# XInC2_Dev_-_SCH.net
KiCad netlist of a schematic drawn in Altium Designer
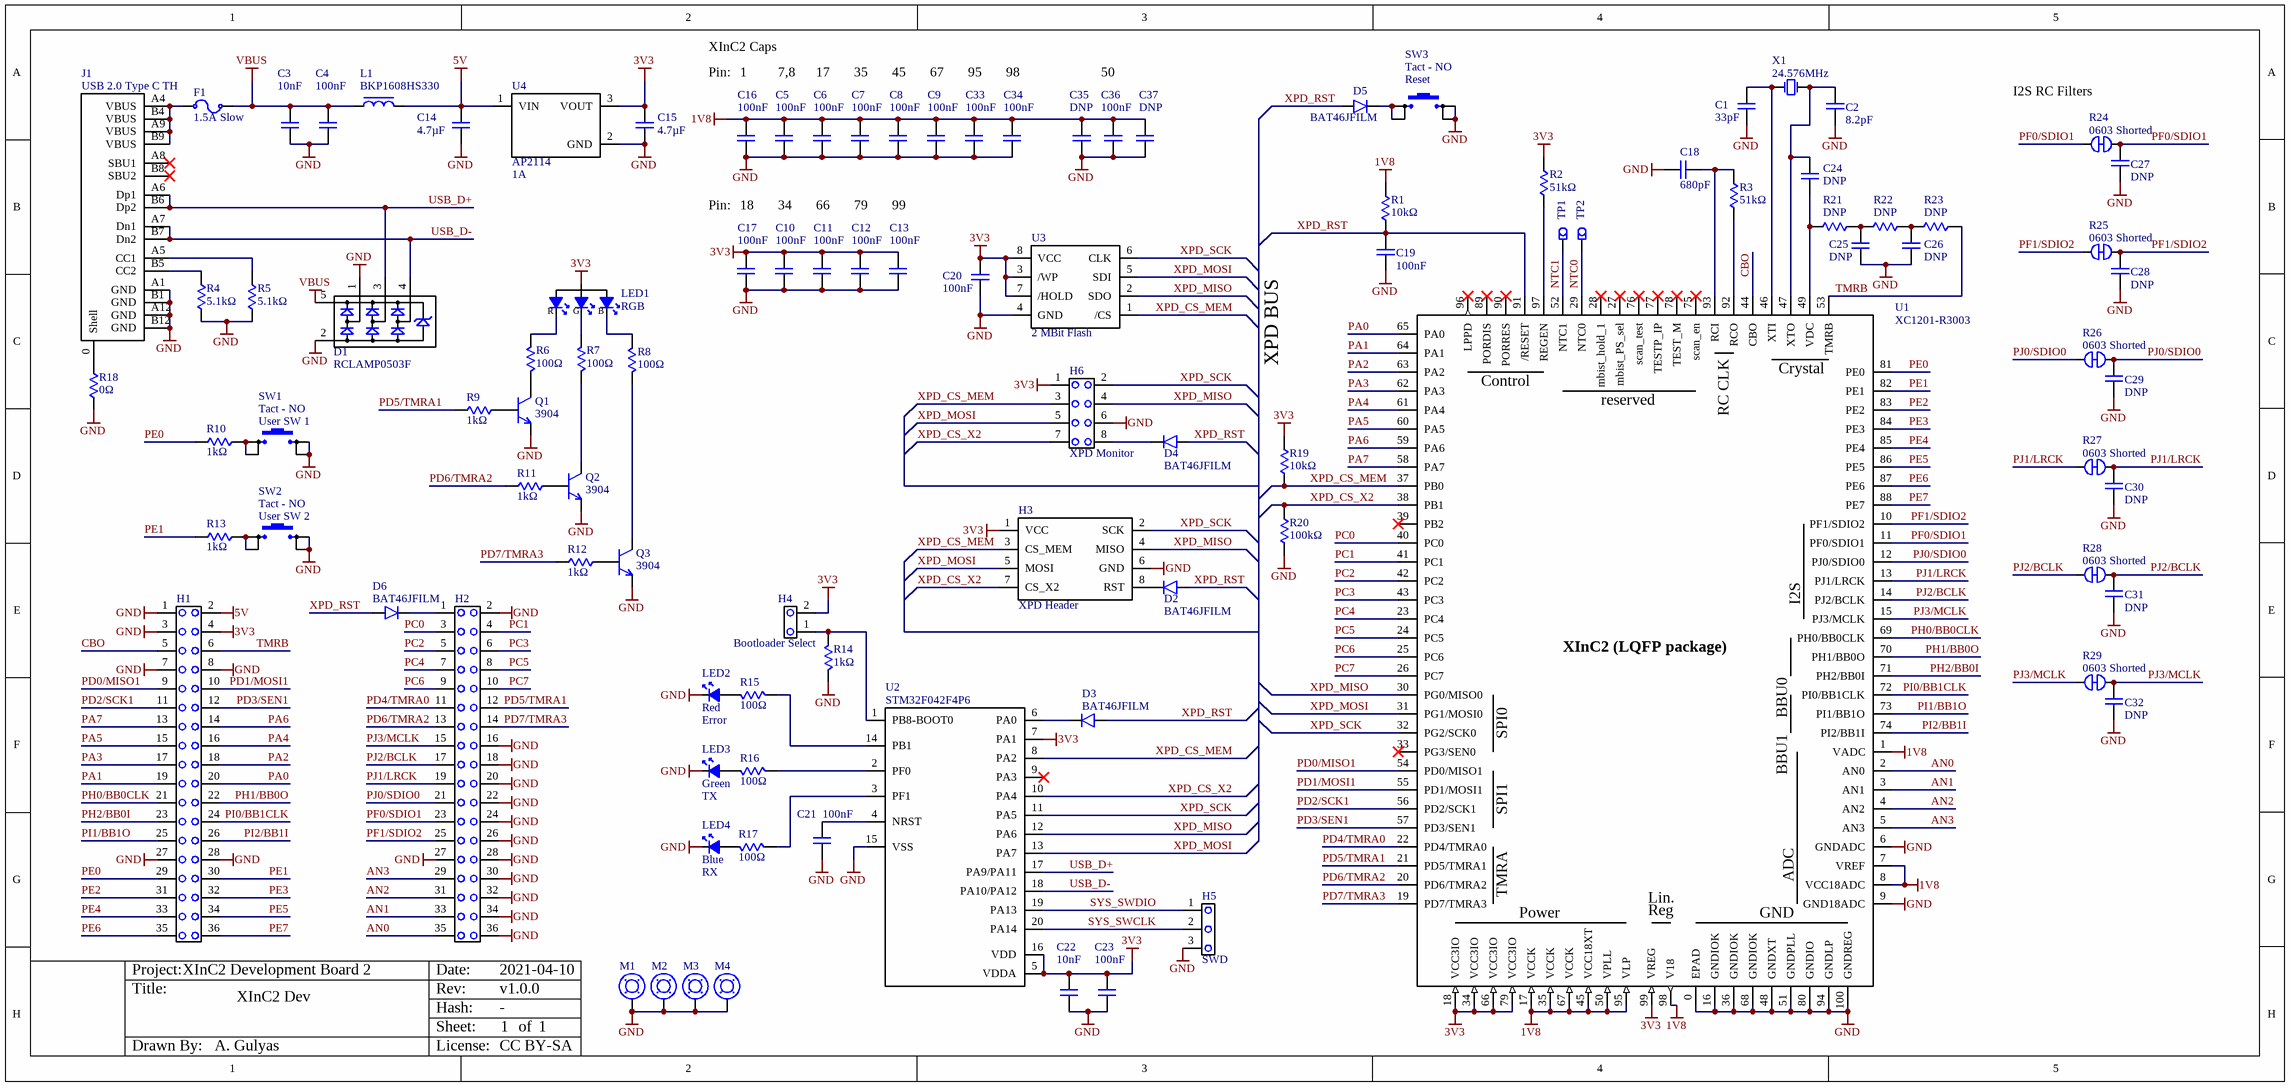
[diagram p0: XInC2 Dev - SCH.SchDoc]

(export (version "E")
  (design (tool "Eeschema 10.0.6"))
  (components
    (comp (ref "C1")
      (value "33pF")
      (footprint "0603 - C")
      (description "CAP CER 33PF 50V C0G/NPO 0603")
      (fields (field (name "MFG") "Yageo") (field (name "TOLERANCE") "±5%"))
      (libsource (lib "Public Library") (part "C - 0603 - 33pF - 16V_1"))
    )
    (comp (ref "C2")
      (value "8.2pF")
      (footprint "0603 - C")
      (description "CAP CER 8.2PF 50V NPO 0603")
      (fields (field (name "MFG") "Yageo") (field (name "TOLERANCE") "±0.25pF"))
      (libsource (lib "Public Library") (part "C - 0603 - 8.2pF - 50V"))
    )
    (comp (ref "C3")
      (value "10nF")
      (footprint "0603 - C")
      (description "CAP CER 10000PF 50V X7R 0603")
      (fields (field (name "MFG") "Yageo") (field (name "TOLERANCE") "±5%"))
      (libsource (lib "Public Library") (part "C - 0603 - 10nF - 50V"))
    )
    (comp (ref "C4")
      (value "100nF")
      (footprint "0603 - C")
      (description "CAP CER 0.1UF 16V X7R 0603")
      (fields (field (name "MFG") "Yageo") (field (name "TOLERANCE") "±10%"))
      (libsource (lib "Public Library") (part "C - 0603 - 100nF - 16V"))
    )
    (comp (ref "C5")
      (value "100nF")
      (footprint "0603 - C")
      (description "CAP CER 0.1UF 16V X7R 0603")
      (fields (field (name "MFG") "Yageo") (field (name "TOLERANCE") "±10%"))
      (libsource (lib "Public Library") (part "C - 0603 - 100nF - 16V"))
    )
    (comp (ref "C6")
      (value "100nF")
      (footprint "0603 - C")
      (description "CAP CER 0.1UF 16V X7R 0603")
      (fields (field (name "MFG") "Yageo") (field (name "TOLERANCE") "±10%"))
      (libsource (lib "Public Library") (part "C - 0603 - 100nF - 16V"))
    )
    (comp (ref "C7")
      (value "100nF")
      (footprint "0603 - C")
      (description "CAP CER 0.1UF 16V X7R 0603")
      (fields (field (name "MFG") "Yageo") (field (name "TOLERANCE") "±10%"))
      (libsource (lib "Public Library") (part "C - 0603 - 100nF - 16V"))
    )
    (comp (ref "C8")
      (value "100nF")
      (footprint "0603 - C")
      (description "CAP CER 0.1UF 16V X7R 0603")
      (fields (field (name "MFG") "Yageo") (field (name "TOLERANCE") "±10%"))
      (libsource (lib "Public Library") (part "C - 0603 - 100nF - 16V"))
    )
    (comp (ref "C9")
      (value "100nF")
      (footprint "0603 - C")
      (description "CAP CER 0.1UF 16V X7R 0603")
      (fields (field (name "MFG") "Yageo") (field (name "TOLERANCE") "±10%"))
      (libsource (lib "Public Library") (part "C - 0603 - 100nF - 16V"))
    )
    (comp (ref "C10")
      (value "100nF")
      (footprint "0603 - C")
      (description "CAP CER 0.1UF 16V X7R 0603")
      (fields (field (name "MFG") "Yageo") (field (name "TOLERANCE") "±10%"))
      (libsource (lib "Public Library") (part "C - 0603 - 100nF - 16V"))
    )
    (comp (ref "C11")
      (value "100nF")
      (footprint "0603 - C")
      (description "CAP CER 0.1UF 16V X7R 0603")
      (fields (field (name "MFG") "Yageo") (field (name "TOLERANCE") "±10%"))
      (libsource (lib "Public Library") (part "C - 0603 - 100nF - 16V"))
    )
    (comp (ref "C12")
      (value "100nF")
      (footprint "0603 - C")
      (description "CAP CER 0.1UF 16V X7R 0603")
      (fields (field (name "MFG") "Yageo") (field (name "TOLERANCE") "±10%"))
      (libsource (lib "Public Library") (part "C - 0603 - 100nF - 16V"))
    )
    (comp (ref "C13")
      (value "100nF")
      (footprint "0603 - C")
      (description "CAP CER 0.1UF 16V X7R 0603")
      (fields (field (name "MFG") "Yageo") (field (name "TOLERANCE") "±10%"))
      (libsource (lib "Public Library") (part "C - 0603 - 100nF - 16V"))
    )
    (comp (ref "C14")
      (value "4.7µF")
      (footprint "0603 - C")
      (description "CAP CER 4.7UF 10V X5R 0603")
      (fields (field (name "MFG") "Yageo") (field (name "TOLERANCE") "±20%"))
      (libsource (lib "Public Library") (part "C - 0603 - 4.7uF - 10V"))
    )
    (comp (ref "C15")
      (value "4.7µF")
      (footprint "0603 - C")
      (description "CAP CER 4.7UF 10V X5R 0603")
      (fields (field (name "MFG") "Yageo") (field (name "TOLERANCE") "±20%"))
      (libsource (lib "Public Library") (part "C - 0603 - 4.7uF - 10V"))
    )
    (comp (ref "C16")
      (value "100nF")
      (footprint "0603 - C")
      (description "CAP CER 0.1UF 16V X7R 0603")
      (fields (field (name "MFG") "Yageo") (field (name "TOLERANCE") "±10%"))
      (libsource (lib "Public Library") (part "C - 0603 - 100nF - 16V"))
    )
    (comp (ref "C17")
      (value "100nF")
      (footprint "0603 - C")
      (description "CAP CER 0.1UF 16V X7R 0603")
      (fields (field (name "MFG") "Yageo") (field (name "TOLERANCE") "±10%"))
      (libsource (lib "Public Library") (part "C - 0603 - 100nF - 16V"))
    )
    (comp (ref "C18")
      (value "680pF")
      (footprint "0603 - C")
      (description "CAP CER 680PF 50V X7R 0603")
      (fields (field (name "MFG") "Yageo") (field (name "TOLERANCE") "±10%"))
      (libsource (lib "Public Library") (part "C - 0603 - 680pF - 50V"))
    )
    (comp (ref "C19")
      (value "100nF")
      (footprint "0603 - C")
      (description "CAP CER 0.1UF 16V X7R 0603")
      (fields (field (name "MFG") "Yageo") (field (name "TOLERANCE") "±10%"))
      (libsource (lib "Public Library") (part "C - 0603 - 100nF - 16V"))
    )
    (comp (ref "C20")
      (value "100nF")
      (footprint "0603 - C")
      (description "CAP CER 0.1UF 16V X7R 0603")
      (fields (field (name "MFG") "Yageo") (field (name "TOLERANCE") "±10%"))
      (libsource (lib "Public Library") (part "C - 0603 - 100nF - 16V"))
    )
    (comp (ref "C21")
      (value "100nF")
      (footprint "0603 - C")
      (description "CAP CER 0.1UF 16V X7R 0603")
      (fields (field (name "MFG") "Yageo") (field (name "TOLERANCE") "±10%"))
      (libsource (lib "Public Library") (part "C - 0603 - 100nF - 16V"))
    )
    (comp (ref "C22")
      (value "10nF")
      (footprint "0603 - C")
      (description "CAP CER 10000PF 50V X7R 0603")
      (fields (field (name "MFG") "Yageo") (field (name "TOLERANCE") "±5%"))
      (libsource (lib "Public Library") (part "C - 0603 - 10nF - 50V"))
    )
    (comp (ref "C23")
      (value "100nF")
      (footprint "0603 - C")
      (description "CAP CER 0.1UF 16V X7R 0603")
      (fields (field (name "MFG") "Yageo") (field (name "TOLERANCE") "±10%"))
      (libsource (lib "Public Library") (part "C - 0603 - 100nF - 16V"))
    )
    (comp (ref "C24")
      (value "DNP")
      (footprint "0603 - C - DNP")
      (description "DNP C 0603")
      (libsource (lib "Public Library") (part "C - 0603 - DNP"))
    )
    (comp (ref "C25")
      (value "DNP")
      (footprint "0603 - C - DNP")
      (description "DNP C 0603")
      (libsource (lib "Public Library") (part "C - 0603 - DNP"))
    )
    (comp (ref "C26")
      (value "DNP")
      (footprint "0603 - C - DNP")
      (description "DNP C 0603")
      (libsource (lib "Public Library") (part "C - 0603 - DNP"))
    )
    (comp (ref "C27")
      (value "DNP")
      (footprint "0603 - C - DNP")
      (description "DNP C 0603")
      (libsource (lib "Public Library") (part "C - 0603 - DNP"))
    )
    (comp (ref "C28")
      (value "DNP")
      (footprint "0603 - C - DNP")
      (description "DNP C 0603")
      (libsource (lib "Public Library") (part "C - 0603 - DNP"))
    )
    (comp (ref "C29")
      (value "DNP")
      (footprint "0603 - C - DNP")
      (description "DNP C 0603")
      (libsource (lib "Public Library") (part "C - 0603 - DNP"))
    )
    (comp (ref "C30")
      (value "DNP")
      (footprint "0603 - C - DNP")
      (description "DNP C 0603")
      (libsource (lib "Public Library") (part "C - 0603 - DNP"))
    )
    (comp (ref "C31")
      (value "DNP")
      (footprint "0603 - C - DNP")
      (description "DNP C 0603")
      (libsource (lib "Public Library") (part "C - 0603 - DNP"))
    )
    (comp (ref "C32")
      (value "DNP")
      (footprint "0603 - C - DNP")
      (description "DNP C 0603")
      (libsource (lib "Public Library") (part "C - 0603 - DNP"))
    )
    (comp (ref "C33")
      (value "100nF")
      (footprint "0603 - C")
      (description "CAP CER 0.1UF 16V X7R 0603")
      (fields (field (name "MFG") "Yageo") (field (name "TOLERANCE") "±10%"))
      (libsource (lib "Public Library") (part "C - 0603 - 100nF - 16V"))
    )
    (comp (ref "C34")
      (value "100nF")
      (footprint "0603 - C")
      (description "CAP CER 0.1UF 16V X7R 0603")
      (fields (field (name "MFG") "Yageo") (field (name "TOLERANCE") "±10%"))
      (libsource (lib "Public Library") (part "C - 0603 - 100nF - 16V"))
    )
    (comp (ref "C35")
      (value "DNP")
      (footprint "0603 - C - DNP")
      (description "DNP C 0603")
      (libsource (lib "Public Library") (part "C - 0603 - DNP"))
    )
    (comp (ref "C36")
      (value "100nF")
      (footprint "0603 - C")
      (description "CAP CER 0.1UF 16V X7R 0603")
      (fields (field (name "MFG") "Yageo") (field (name "TOLERANCE") "±10%"))
      (libsource (lib "Public Library") (part "C - 0603 - 100nF - 16V"))
    )
    (comp (ref "C37")
      (value "DNP")
      (footprint "0603 - C - DNP")
      (description "DNP C 0603")
      (libsource (lib "Public Library") (part "C - 0603 - DNP"))
    )
    (comp (ref "D1")
      (value "RCLAMP0503F")
      (footprint "SOT 353")
      (description "TVS DIODE 5V 25V SC70-5")
      (fields (field (name "MFG") "Semtech Corp"))
      (libsource (lib "Public Library") (part "TVS - USB - RCLAMP0503F"))
    )
    (comp (ref "D2")
      (value "BAT46JFILM")
      (footprint "SOD 323")
      (description "DIODE SCHOTTKY 100V 150MA SOD323")
      (fields (field (name "MFG") "ST"))
      (libsource (lib "Public Library") (part "D - BAT46JFILM"))
    )
    (comp (ref "D3")
      (value "BAT46JFILM")
      (footprint "SOD 323")
      (description "DIODE SCHOTTKY 100V 150MA SOD323")
      (fields (field (name "MFG") "ST"))
      (libsource (lib "Public Library") (part "D - BAT46JFILM"))
    )
    (comp (ref "D4")
      (value "BAT46JFILM")
      (footprint "SOD 323 and 0603")
      (description "DIODE SCHOTTKY 100V 150MA SOD323")
      (fields (field (name "MFG") "ST"))
      (libsource (lib "Public Library") (part "D - BAT46JFILM"))
    )
    (comp (ref "D5")
      (value "BAT46JFILM")
      (footprint "SOD 323")
      (description "DIODE SCHOTTKY 100V 150MA SOD323")
      (fields (field (name "MFG") "ST"))
      (libsource (lib "Public Library") (part "D - BAT46JFILM"))
    )
    (comp (ref "D6")
      (value "BAT46JFILM")
      (footprint "SOD 323")
      (description "DIODE SCHOTTKY 100V 150MA SOD323")
      (fields (field (name "MFG") "ST"))
      (libsource (lib "Public Library") (part "D - BAT46JFILM"))
    )
    (comp (ref "F1")
      (value "1.5A Slow")
      (footprint "Fuse - C1T Series")
      (description "FUSE 1.5A 63VAC/DC SLOW 1206")
      (fields (field (name "MFG") "Bel Fuse Inc."))
      (libsource (lib "Public Library") (part "Fuse - 1.5A slow"))
    )
    (comp (ref "H1")
      (value "SSQ-118-03-T-D")
      (footprint "H - 100mil - 2x18 - Stack - bottom insert")
      (description "CONN RCPT 36POS 0.1 TIN PCB")
      (fields (field (name "MFG") "Samtec"))
      (libsource (lib "Public Library") (part "H - 100mil - Stack - 2x18"))
    )
    (comp (ref "H2")
      (value "SSQ-118-03-T-D")
      (footprint "H - 100mil - 2x18 - Stack - bottom insert")
      (description "CONN RCPT 36POS 0.1 TIN PCB")
      (fields (field (name "MFG") "Samtec"))
      (libsource (lib "Public Library") (part "H - 100mil - Stack - 2x18"))
    )
    (comp (ref "H3")
      (value "XPD Header")
      (footprint "H - XPD")
      (description "CONN HEADER SMD 8POS 1.27MM")
      (fields (field (name "MFG") "Samtec Inc."))
      (libsource (lib "Public Library") (part "H - XPD - SMT"))
    )
    (comp (ref "H4")
      (value "H - 100mil - M - TH - 1x2")
      (footprint "H - 100mil - 1x2 - TH")
      (description "CONN HEADER VERT 2POS 2.54MM")
      (fields (field (name "PURPOSE") "Bootloader Select"))
      (libsource (lib "Public Library") (part "H - 100mil - M - TH - 1x2"))
    )
    (comp (ref "H5")
      (value "H - 100mil - M - TH - 1x3")
      (footprint "H - 100mil - 1x3 - TH")
      (description "CONN HEADER VERT 3POS 2.54MM")
      (fields (field (name "PURPOSE") "SWD"))
      (libsource (lib "Public Library") (part "H - 100mil - M - TH - 1x3"))
    )
    (comp (ref "H6")
      (value "H - 100mil - M - TH - 2x4")
      (footprint "H - 100mil - 2x4 - TH - DNP")
      (fields (field (name "PURPOSE") "XPD Monitor"))
      (libsource (lib "Public Library") (part "H - 100mil - M - TH - 2x4"))
    )
    (comp (ref "J1")
      (value "USB 2.0 Type C TH")
      (footprint "Jack - USB C - 2.0 - TH")
      (description "CONN RCPT USB2.0 TYPEC 16POS")
      (fields (field (name "MFG") "GCT"))
      (libsource (lib "Public Library") (part "Jack - USB C - USB4085"))
    )
    (comp (ref "L1")
      (value "BKP1608HS330")
      (footprint "0603 - R")
      (description "FERRITE BEAD 33 OHM 0603 1LN")
      (fields (field (name "MFG") "Taiyo Yuden"))
      (libsource (lib "Public Library") (part "Ferrite - 0603 - 33 ohm"))
    )
    (comp (ref "LED1")
      (value "RGB")
      (footprint "LED - RGB - 0606")
      (description "LED RGB CLEAR 4SMD")
      (fields (field (name "MFG") "Everlight Electronics"))
      (libsource (lib "Public Library") (part "LED - RGB"))
    )
    (comp (ref "LED2")
      (value "Red")
      (footprint "LED - Red - 0603")
      (description "LED RED CLEAR CHIP SMD")
      (fields (field (name "MFG") "Lite-On Inc.") (field (name "PURPOSE") "Error"))
      (libsource (lib "Public Library") (part "LED - Red"))
    )
    (comp (ref "LED3")
      (value "Green")
      (footprint "LED - Green - 0603")
      (description "LED GREEN CLEAR CHIP SMD")
      (fields (field (name "MFG") "Lite-On Inc.") (field (name "PURPOSE") "TX"))
      (libsource (lib "Public Library") (part "LED - Green"))
    )
    (comp (ref "LED4")
      (value "Blue")
      (footprint "LED - Blue - 0603")
      (description "LED BLUE CLEAR CHIP SMD")
      (fields (field (name "MFG") "Lite-On Inc.") (field (name "PURPOSE") "RX"))
      (libsource (lib "Public Library") (part "LED - Blue"))
    )
    (comp (ref "M1")
      (value "Mech - Bolt Hole - M3")
      (footprint "Bolt Hole - M3")
      (libsource (lib "Public Library") (part "Mech - Bolt Hole - M3"))
    )
    (comp (ref "M2")
      (value "Mech - Bolt Hole - M3")
      (footprint "Bolt Hole - M3")
      (libsource (lib "Public Library") (part "Mech - Bolt Hole - M3"))
    )
    (comp (ref "M3")
      (value "Mech - Bolt Hole - M3")
      (footprint "Bolt Hole - M3")
      (libsource (lib "Public Library") (part "Mech - Bolt Hole - M3"))
    )
    (comp (ref "M4")
      (value "Mech - Bolt Hole - M3")
      (footprint "Bolt Hole - M3")
      (libsource (lib "Public Library") (part "Mech - Bolt Hole - M3"))
    )
    (comp (ref "Q1")
      (value "3904")
      (footprint "SOT 23 - NPN - MCC")
      (description "TRANS NPN 40V 0.2A SOT23")
      (fields (field (name "MFG") "Micro Commercial"))
      (libsource (lib "Public Library") (part "Q - NPN - MMBT3904"))
    )
    (comp (ref "Q2")
      (value "3904")
      (footprint "SOT 23 - NPN - MCC")
      (description "TRANS NPN 40V 0.2A SOT23")
      (fields (field (name "MFG") "Micro Commercial"))
      (libsource (lib "Public Library") (part "Q - NPN - MMBT3904"))
    )
    (comp (ref "Q3")
      (value "3904")
      (footprint "SOT 23 - NPN - MCC")
      (description "TRANS NPN 40V 0.2A SOT23")
      (fields (field (name "MFG") "Micro Commercial"))
      (libsource (lib "Public Library") (part "Q - NPN - MMBT3904"))
    )
    (comp (ref "R1")
      (value "10kΩ")
      (footprint "0603 - R")
      (description "RES SMD 10K OHM 5% 1/10W 0603")
      (fields (field (name "MFG") "Yageo") (field (name "POWER") "0.1W"))
      (libsource (lib "Public Library") (part "R - 0603 - 10k"))
    )
    (comp (ref "R2")
      (value "51kΩ")
      (footprint "0603 - R")
      (description "RES SMD 51K OHM 5% 1/10W 0603")
      (fields (field (name "MFG") "Yageo") (field (name "POWER") "0.1W"))
      (libsource (lib "Public Library") (part "R - 0603 - 51k"))
    )
    (comp (ref "R3")
      (value "51kΩ")
      (footprint "0603 - R")
      (description "RES SMD 51K OHM 5% 1/10W 0603")
      (fields (field (name "MFG") "Yageo") (field (name "POWER") "0.1W"))
      (libsource (lib "Public Library") (part "R - 0603 - 51k"))
    )
    (comp (ref "R4")
      (value "5.1kΩ")
      (footprint "0603 - R")
      (description "RES SMD 5.1K OHM 5% 1/10W 0603")
      (fields (field (name "MFG") "Yageo") (field (name "POWER") "0.1W"))
      (libsource (lib "Public Library") (part "R - 0603 - 5.1k"))
    )
    (comp (ref "R5")
      (value "5.1kΩ")
      (footprint "0603 - R")
      (description "RES SMD 5.1K OHM 5% 1/10W 0603")
      (fields (field (name "MFG") "Yageo") (field (name "POWER") "0.1W"))
      (libsource (lib "Public Library") (part "R - 0603 - 5.1k"))
    )
    (comp (ref "R6")
      (value "100Ω")
      (footprint "0603 - R")
      (description "RES SMD 100 OHM 5% 1/10W 0603")
      (fields (field (name "MFG") "Yageo") (field (name "POWER") "0.1W"))
      (libsource (lib "Public Library") (part "R - 0603 - 100R"))
    )
    (comp (ref "R7")
      (value "100Ω")
      (footprint "0603 - R")
      (description "RES SMD 100 OHM 5% 1/10W 0603")
      (fields (field (name "MFG") "Yageo") (field (name "POWER") "0.1W"))
      (libsource (lib "Public Library") (part "R - 0603 - 100R"))
    )
    (comp (ref "R8")
      (value "100Ω")
      (footprint "0603 - R")
      (description "RES SMD 100 OHM 5% 1/10W 0603")
      (fields (field (name "MFG") "Yageo") (field (name "POWER") "0.1W"))
      (libsource (lib "Public Library") (part "R - 0603 - 100R"))
    )
    (comp (ref "R9")
      (value "1kΩ")
      (footprint "0603 - R")
      (description "RES SMD 1K OHM 5% 1/10W 0603")
      (fields (field (name "MFG") "Yageo") (field (name "POWER") "0.1W"))
      (libsource (lib "Public Library") (part "R - 0603 - 1k"))
    )
    (comp (ref "R10")
      (value "1kΩ")
      (footprint "0603 - R")
      (description "RES SMD 1K OHM 5% 1/10W 0603")
      (fields (field (name "MFG") "Yageo") (field (name "POWER") "0.1W"))
      (libsource (lib "Public Library") (part "R - 0603 - 1k"))
    )
    (comp (ref "R11")
      (value "1kΩ")
      (footprint "0603 - R")
      (description "RES SMD 1K OHM 5% 1/10W 0603")
      (fields (field (name "MFG") "Yageo") (field (name "POWER") "0.1W"))
      (libsource (lib "Public Library") (part "R - 0603 - 1k"))
    )
    (comp (ref "R12")
      (value "1kΩ")
      (footprint "0603 - R")
      (description "RES SMD 1K OHM 5% 1/10W 0603")
      (fields (field (name "MFG") "Yageo") (field (name "POWER") "0.1W"))
      (libsource (lib "Public Library") (part "R - 0603 - 1k"))
    )
    (comp (ref "R13")
      (value "1kΩ")
      (footprint "0603 - R")
      (description "RES SMD 1K OHM 5% 1/10W 0603")
      (fields (field (name "MFG") "Yageo") (field (name "POWER") "0.1W"))
      (libsource (lib "Public Library") (part "R - 0603 - 1k"))
    )
    (comp (ref "R14")
      (value "1kΩ")
      (footprint "0603 - R")
      (description "RES SMD 1K OHM 5% 1/10W 0603")
      (fields (field (name "MFG") "Yageo") (field (name "POWER") "0.1W"))
      (libsource (lib "Public Library") (part "R - 0603 - 1k"))
    )
    (comp (ref "R15")
      (value "100Ω")
      (footprint "0603 - R")
      (description "RES SMD 100 OHM 5% 1/10W 0603")
      (fields (field (name "MFG") "Yageo") (field (name "POWER") "0.1W"))
      (libsource (lib "Public Library") (part "R - 0603 - 100R"))
    )
    (comp (ref "R16")
      (value "100Ω")
      (footprint "0603 - R")
      (description "RES SMD 100 OHM 5% 1/10W 0603")
      (fields (field (name "MFG") "Yageo") (field (name "POWER") "0.1W"))
      (libsource (lib "Public Library") (part "R - 0603 - 100R"))
    )
    (comp (ref "R17")
      (value "100Ω")
      (footprint "0603 - R")
      (description "RES SMD 100 OHM 5% 1/10W 0603")
      (fields (field (name "MFG") "Yageo") (field (name "POWER") "0.1W"))
      (libsource (lib "Public Library") (part "R - 0603 - 100R"))
    )
    (comp (ref "R18")
      (value "0Ω")
      (footprint "0603 - R")
      (description "RES SMD 0 OHM JUMPER 1/10W 0603")
      (fields (field (name "MFG") "Yageo") (field (name "POWER") "0.1W"))
      (libsource (lib "Public Library") (part "Jumper - 0603"))
    )
    (comp (ref "R19")
      (value "10kΩ")
      (footprint "0603 - R")
      (description "RES SMD 10K OHM 5% 1/10W 0603")
      (fields (field (name "MFG") "Yageo") (field (name "POWER") "0.1W"))
      (libsource (lib "Public Library") (part "R - 0603 - 10k"))
    )
    (comp (ref "R20")
      (value "100kΩ")
      (footprint "0603 - R")
      (description "RES SMD 100K OHM 5% 1/10W 0603")
      (fields (field (name "MFG") "Yageo") (field (name "POWER") "0.1W"))
      (libsource (lib "Public Library") (part "R - 0603 - 100k"))
    )
    (comp (ref "R21")
      (value "DNP")
      (footprint "0603 - R - DNP")
      (description "DNP R 0603")
      (libsource (lib "Public Library") (part "R - 0603 - DNP"))
    )
    (comp (ref "R22")
      (value "DNP")
      (footprint "0603 - R - DNP")
      (description "DNP R 0603")
      (libsource (lib "Public Library") (part "R - 0603 - DNP"))
    )
    (comp (ref "R23")
      (value "DNP")
      (footprint "0603 - R - DNP")
      (description "DNP R 0603")
      (libsource (lib "Public Library") (part "R - 0603 - DNP"))
    )
    (comp (ref "R24")
      (value "0603 Shorted")
      (footprint "0603 - R - shorted jumper")
      (description "DNP: 0603 Resistor with the pads shorted")
      (fields (field (name "MFG") "Yageo") (field (name "POWER") "0.1W"))
      (libsource (lib "Public Library") (part "Jumper - 0603 - Shorted"))
    )
    (comp (ref "R25")
      (value "0603 Shorted")
      (footprint "0603 - R - shorted jumper")
      (description "DNP: 0603 Resistor with the pads shorted")
      (fields (field (name "MFG") "Yageo") (field (name "POWER") "0.1W"))
      (libsource (lib "Public Library") (part "Jumper - 0603 - Shorted"))
    )
    (comp (ref "R26")
      (value "0603 Shorted")
      (footprint "0603 - R - shorted jumper")
      (description "DNP: 0603 Resistor with the pads shorted")
      (fields (field (name "MFG") "Yageo") (field (name "POWER") "0.1W"))
      (libsource (lib "Public Library") (part "Jumper - 0603 - Shorted"))
    )
    (comp (ref "R27")
      (value "0603 Shorted")
      (footprint "0603 - R - shorted jumper")
      (description "DNP: 0603 Resistor with the pads shorted")
      (fields (field (name "MFG") "Yageo") (field (name "POWER") "0.1W"))
      (libsource (lib "Public Library") (part "Jumper - 0603 - Shorted"))
    )
    (comp (ref "R28")
      (value "0603 Shorted")
      (footprint "0603 - R - shorted jumper")
      (description "DNP: 0603 Resistor with the pads shorted")
      (fields (field (name "MFG") "Yageo") (field (name "POWER") "0.1W"))
      (libsource (lib "Public Library") (part "Jumper - 0603 - Shorted"))
    )
    (comp (ref "R29")
      (value "0603 Shorted")
      (footprint "0603 - R - shorted jumper")
      (description "DNP: 0603 Resistor with the pads shorted")
      (fields (field (name "MFG") "Yageo") (field (name "POWER") "0.1W"))
      (libsource (lib "Public Library") (part "Jumper - 0603 - Shorted"))
    )
    (comp (ref "SW1")
      (value "Tact - NO")
      (footprint "SW - Tact - SMT")
      (description "SWITCH TACTILE SPST-NO 3VA 28V")
      (fields (field (name "PURPOSE") "User SW 1") (field (name "MFG") "NKK Switches"))
      (libsource (lib "Public Library") (part "SW - Tactile - HP0315AFKP2-R"))
    )
    (comp (ref "SW2")
      (value "Tact - NO")
      (footprint "SW - Tact - SMT")
      (description "SWITCH TACTILE SPST-NO 3VA 28V")
      (fields (field (name "PURPOSE") "User SW 2") (field (name "MFG") "NKK Switches"))
      (libsource (lib "Public Library") (part "SW - Tactile - HP0315AFKP2-R"))
    )
    (comp (ref "SW3")
      (value "Tact - NO")
      (footprint "SW - Tact - SMT")
      (description "SWITCH TACTILE SPST-NO 3VA 28V")
      (fields (field (name "PURPOSE") "Reset") (field (name "MFG") "NKK Switches"))
      (libsource (lib "Public Library") (part "SW - Tactile - HP0315AFKP2-R"))
    )
    (comp (ref "TP1")
      (value "Signal")
      (footprint "TP - TH - 0.6mm")
      (libsource (lib "Public Library") (part "TP - TH - 0.6 mm"))
    )
    (comp (ref "TP2")
      (value "Signal")
      (footprint "TP - TH - 0.6mm")
      (libsource (lib "Public Library") (part "TP - TH - 0.6 mm"))
    )
    (comp (ref "U1")
      (value "XC1201-R3003")
      (footprint "XInC2 LQFP 100")
      (description "XInC2 Multi-Threaded µC LQFP")
      (fields (field (name "MFG") "Eleven Engineering"))
      (libsource (lib "Public Library") (part "uC - XInC2 - LQFP"))
    )
    (comp (ref "U2")
      (value "STM32F042F4P6")
      (footprint "TSSOP 20")
      (description "IC MCU 32BIT 16KB FLASH 20TSSOP")
      (fields (field (name "MFG") "ST"))
      (libsource (lib "Public Library") (part "uC - STM32F042F4P6"))
    )
    (comp (ref "U3")
      (value "2 MBit Flash")
      (footprint "SOIC 8")
      (description "IC FLASH 2MBIT SPI 104MHZ 8SOIC")
      (fields (field (name "MFG") "Winbond Electronics"))
      (libsource (lib "Public Library") (part "Mem - Flash - 2 MBit - W25Q20CL"))
    )
    (comp (ref "U4")
      (value "AP2114")
      (footprint "SOT 223")
      (description "IC REG LINEAR 3.3V 1A SOT223")
      (fields (field (name "MFG") "Diodes Inc") (field (name "CURRENT - OUTPUT") "1A"))
      (libsource (lib "Public Library") (part "Reg - Lin - 3.3V - AP2114"))
    )
    (comp (ref "X1")
      (value "24.576MHz")
      (footprint "X - HC-49/US")
      (description "CRYSTAL 24.576MHZ SMD")
      (fields (field (name "MFG") "Huijing"))
      (libsource (lib "Public Library") (part "X - 20 MHz - HJ24.576"))
    )
  )
  (nets
    (net (code "1") (name "/AN0") (class "Default")
      (node (ref "H2") (pin "35") (pinfunction "35_35") (pintype "passive"))
      (node (ref "U1") (pin "2") (pinfunction "AN0_2") (pintype "passive"))
    )
    (net (code "2") (name "/AN1") (class "Default")
      (node (ref "H2") (pin "33") (pinfunction "33_33") (pintype "passive"))
      (node (ref "U1") (pin "3") (pinfunction "AN1_3") (pintype "passive"))
    )
    (net (code "3") (name "/AN2") (class "Default")
      (node (ref "H2") (pin "31") (pinfunction "31_31") (pintype "passive"))
      (node (ref "U1") (pin "4") (pinfunction "AN2_4") (pintype "passive"))
    )
    (net (code "4") (name "/AN3") (class "Default")
      (node (ref "H2") (pin "29") (pinfunction "29_29") (pintype "passive"))
      (node (ref "U1") (pin "5") (pinfunction "AN3_5") (pintype "passive"))
    )
    (net (code "5") (name "/CBO") (class "Default")
      (node (ref "H1") (pin "5") (pinfunction "5_5") (pintype "passive"))
      (node (ref "U1") (pin "44") (pinfunction "CBO_44") (pintype "passive"))
    )
    (net (code "6") (name "/NTC0") (class "Default")
      (node (ref "TP2") (pin "1") (pinfunction "1_1") (pintype "passive"))
      (node (ref "U1") (pin "29") (pinfunction "NTC0_29") (pintype "passive"))
    )
    (net (code "7") (name "/NTC1") (class "Default")
      (node (ref "TP1") (pin "1") (pinfunction "1_1") (pintype "passive"))
      (node (ref "U1") (pin "52") (pinfunction "NTC1_52") (pintype "passive"))
    )
    (net (code "8") (name "/PA0") (class "Default")
      (node (ref "H1") (pin "20") (pinfunction "20_20") (pintype "passive"))
      (node (ref "U1") (pin "65") (pinfunction "PA0_65") (pintype "passive"))
    )
    (net (code "9") (name "/PA1") (class "Default")
      (node (ref "H1") (pin "19") (pinfunction "19_19") (pintype "passive"))
      (node (ref "U1") (pin "64") (pinfunction "PA1_64") (pintype "passive"))
    )
    (net (code "10") (name "/PA2") (class "Default")
      (node (ref "H1") (pin "18") (pinfunction "18_18") (pintype "passive"))
      (node (ref "U1") (pin "63") (pinfunction "PA2_63") (pintype "passive"))
    )
    (net (code "11") (name "/PA3") (class "Default")
      (node (ref "H1") (pin "17") (pinfunction "17_17") (pintype "passive"))
      (node (ref "U1") (pin "62") (pinfunction "PA3_62") (pintype "passive"))
    )
    (net (code "12") (name "/PA4") (class "Default")
      (node (ref "H1") (pin "16") (pinfunction "16_16") (pintype "passive"))
      (node (ref "U1") (pin "61") (pinfunction "PA4_61") (pintype "passive"))
    )
    (net (code "13") (name "/PA5") (class "Default")
      (node (ref "H1") (pin "15") (pinfunction "15_15") (pintype "passive"))
      (node (ref "U1") (pin "60") (pinfunction "PA5_60") (pintype "passive"))
    )
    (net (code "14") (name "/PA6") (class "Default")
      (node (ref "H1") (pin "14") (pinfunction "14_14") (pintype "passive"))
      (node (ref "U1") (pin "59") (pinfunction "PA6_59") (pintype "passive"))
    )
    (net (code "15") (name "/PA7") (class "Default")
      (node (ref "H1") (pin "13") (pinfunction "13_13") (pintype "passive"))
      (node (ref "U1") (pin "58") (pinfunction "PA7_58") (pintype "passive"))
    )
    (net (code "16") (name "/PC0") (class "Default")
      (node (ref "H2") (pin "3") (pinfunction "3_3") (pintype "passive"))
      (node (ref "U1") (pin "40") (pinfunction "PC0_40") (pintype "passive"))
    )
    (net (code "17") (name "/PC1") (class "Default")
      (node (ref "H2") (pin "4") (pinfunction "4_4") (pintype "passive"))
      (node (ref "U1") (pin "41") (pinfunction "PC1_41") (pintype "passive"))
    )
    (net (code "18") (name "/PC2") (class "Default")
      (node (ref "H2") (pin "5") (pinfunction "5_5") (pintype "passive"))
      (node (ref "U1") (pin "42") (pinfunction "PC2_42") (pintype "passive"))
    )
    (net (code "19") (name "/PC3") (class "Default")
      (node (ref "H2") (pin "6") (pinfunction "6_6") (pintype "passive"))
      (node (ref "U1") (pin "43") (pinfunction "PC3_43") (pintype "passive"))
    )
    (net (code "20") (name "/PC4") (class "Default")
      (node (ref "H2") (pin "7") (pinfunction "7_7") (pintype "passive"))
      (node (ref "U1") (pin "23") (pinfunction "PC4_23") (pintype "passive"))
    )
    (net (code "21") (name "/PC5") (class "Default")
      (node (ref "H2") (pin "8") (pinfunction "8_8") (pintype "passive"))
      (node (ref "U1") (pin "24") (pinfunction "PC5_24") (pintype "passive"))
    )
    (net (code "22") (name "/PC6") (class "Default")
      (node (ref "H2") (pin "9") (pinfunction "9_9") (pintype "passive"))
      (node (ref "U1") (pin "25") (pinfunction "PC6_25") (pintype "passive"))
    )
    (net (code "23") (name "/PC7") (class "Default")
      (node (ref "H2") (pin "10") (pinfunction "10_10") (pintype "passive"))
      (node (ref "U1") (pin "26") (pinfunction "PC7_26") (pintype "passive"))
    )
    (net (code "24") (name "/PD0{slash}MISO1") (class "Default")
      (node (ref "H1") (pin "9") (pinfunction "9_9") (pintype "passive"))
      (node (ref "U1") (pin "54") (pinfunction "PD0/MISO1_54") (pintype "passive"))
    )
    (net (code "25") (name "/PD1{slash}MOSI1") (class "Default")
      (node (ref "H1") (pin "10") (pinfunction "10_10") (pintype "passive"))
      (node (ref "U1") (pin "55") (pinfunction "PD1/MOSI1_55") (pintype "passive"))
    )
    (net (code "26") (name "/PD2{slash}SCK1") (class "Default")
      (node (ref "H1") (pin "11") (pinfunction "11_11") (pintype "passive"))
      (node (ref "U1") (pin "56") (pinfunction "PD2/SCK1_56") (pintype "passive"))
    )
    (net (code "27") (name "/PD3{slash}SEN1") (class "Default")
      (node (ref "H1") (pin "12") (pinfunction "12_12") (pintype "passive"))
      (node (ref "U1") (pin "57") (pinfunction "PD3/SEN1_57") (pintype "passive"))
    )
    (net (code "28") (name "/PD4{slash}TMRA0") (class "Default")
      (node (ref "H2") (pin "11") (pinfunction "11_11") (pintype "passive"))
      (node (ref "U1") (pin "22") (pinfunction "PD4/TMRA0_22") (pintype "passive"))
    )
    (net (code "29") (name "/PD5{slash}TMRA1") (class "Default")
      (node (ref "H2") (pin "12") (pinfunction "12_12") (pintype "passive"))
      (node (ref "R9") (pin "1") (pinfunction "1_1") (pintype "passive"))
      (node (ref "U1") (pin "21") (pinfunction "PD5/TMRA1_21") (pintype "passive"))
    )
    (net (code "30") (name "/PD6{slash}TMRA2") (class "Default")
      (node (ref "H2") (pin "13") (pinfunction "13_13") (pintype "passive"))
      (node (ref "R11") (pin "1") (pinfunction "1_1") (pintype "passive"))
      (node (ref "U1") (pin "20") (pinfunction "PD6/TMRA2_20") (pintype "passive"))
    )
    (net (code "31") (name "/PD7{slash}TMRA3") (class "Default")
      (node (ref "H2") (pin "14") (pinfunction "14_14") (pintype "passive"))
      (node (ref "R12") (pin "1") (pinfunction "1_1") (pintype "passive"))
      (node (ref "U1") (pin "19") (pinfunction "PD7/TMRA3_19") (pintype "passive"))
    )
    (net (code "32") (name "/PE0") (class "Default")
      (node (ref "H1") (pin "29") (pinfunction "29_29") (pintype "passive"))
      (node (ref "R10") (pin "1") (pinfunction "1_1") (pintype "passive"))
      (node (ref "U1") (pin "81") (pinfunction "PE0_81") (pintype "passive"))
    )
    (net (code "33") (name "/PE1") (class "Default")
      (node (ref "H1") (pin "30") (pinfunction "30_30") (pintype "passive"))
      (node (ref "R13") (pin "1") (pinfunction "1_1") (pintype "passive"))
      (node (ref "U1") (pin "82") (pinfunction "PE1_82") (pintype "passive"))
    )
    (net (code "34") (name "/PE2") (class "Default")
      (node (ref "H1") (pin "31") (pinfunction "31_31") (pintype "passive"))
      (node (ref "U1") (pin "83") (pinfunction "PE2_83") (pintype "passive"))
    )
    (net (code "35") (name "/PE3") (class "Default")
      (node (ref "H1") (pin "32") (pinfunction "32_32") (pintype "passive"))
      (node (ref "U1") (pin "84") (pinfunction "PE3_84") (pintype "passive"))
    )
    (net (code "36") (name "/PE4") (class "Default")
      (node (ref "H1") (pin "33") (pinfunction "33_33") (pintype "passive"))
      (node (ref "U1") (pin "85") (pinfunction "PE4_85") (pintype "passive"))
    )
    (net (code "37") (name "/PE5") (class "Default")
      (node (ref "H1") (pin "34") (pinfunction "34_34") (pintype "passive"))
      (node (ref "U1") (pin "86") (pinfunction "PE5_86") (pintype "passive"))
    )
    (net (code "38") (name "/PE6") (class "Default")
      (node (ref "H1") (pin "35") (pinfunction "35_35") (pintype "passive"))
      (node (ref "U1") (pin "87") (pinfunction "PE6_87") (pintype "passive"))
    )
    (net (code "39") (name "/PE7") (class "Default")
      (node (ref "H1") (pin "36") (pinfunction "36_36") (pintype "passive"))
      (node (ref "U1") (pin "88") (pinfunction "PE7_88") (pintype "passive"))
    )
    (net (code "40") (name "/PF0{slash}SDIO1") (class "Default")
      (node (ref "C27") (pin "1") (pinfunction "1_1") (pintype "passive"))
      (node (ref "H2") (pin "23") (pinfunction "23_23") (pintype "passive"))
      (node (ref "R24") (pin "1") (pinfunction "1_1") (pintype "passive"))
      (node (ref "R24") (pin "2") (pinfunction "2_2") (pintype "passive"))
      (node (ref "U1") (pin "11") (pinfunction "PF0/SDIO1_11") (pintype "passive"))
    )
    (net (code "41") (name "/PF1{slash}SDIO2") (class "Default")
      (node (ref "C28") (pin "1") (pinfunction "1_1") (pintype "passive"))
      (node (ref "H2") (pin "25") (pinfunction "25_25") (pintype "passive"))
      (node (ref "R25") (pin "1") (pinfunction "1_1") (pintype "passive"))
      (node (ref "R25") (pin "2") (pinfunction "2_2") (pintype "passive"))
      (node (ref "U1") (pin "10") (pinfunction "PF1/SDIO2_10") (pintype "passive"))
    )
    (net (code "42") (name "/PH0{slash}BB0CLK") (class "Default")
      (node (ref "H1") (pin "21") (pinfunction "21_21") (pintype "passive"))
      (node (ref "U1") (pin "69") (pinfunction "PH0/BB0CLK_69") (pintype "passive"))
    )
    (net (code "43") (name "/PH1{slash}BB0O") (class "Default")
      (node (ref "H1") (pin "22") (pinfunction "22_22") (pintype "passive"))
      (node (ref "U1") (pin "70") (pinfunction "PH1/BB0O_70") (pintype "passive"))
    )
    (net (code "44") (name "/PH2{slash}BB0I") (class "Default")
      (node (ref "H1") (pin "23") (pinfunction "23_23") (pintype "passive"))
      (node (ref "U1") (pin "71") (pinfunction "PH2/BB0I_71") (pintype "passive"))
    )
    (net (code "45") (name "/PI0{slash}BB1CLK") (class "Default")
      (node (ref "H1") (pin "24") (pinfunction "24_24") (pintype "passive"))
      (node (ref "U1") (pin "72") (pinfunction "PI0/BB1CLK_72") (pintype "passive"))
    )
    (net (code "46") (name "/PI1{slash}BB1O") (class "Default")
      (node (ref "H1") (pin "25") (pinfunction "25_25") (pintype "passive"))
      (node (ref "U1") (pin "73") (pinfunction "PI1/BB1O_73") (pintype "passive"))
    )
    (net (code "47") (name "/PI2{slash}BB1I") (class "Default")
      (node (ref "H1") (pin "26") (pinfunction "26_26") (pintype "passive"))
      (node (ref "U1") (pin "74") (pinfunction "PI2/BB1I_74") (pintype "passive"))
    )
    (net (code "48") (name "/PJ0{slash}SDIO0") (class "Default")
      (node (ref "C29") (pin "1") (pinfunction "1_1") (pintype "passive"))
      (node (ref "H2") (pin "21") (pinfunction "21_21") (pintype "passive"))
      (node (ref "R26") (pin "1") (pinfunction "1_1") (pintype "passive"))
      (node (ref "R26") (pin "2") (pinfunction "2_2") (pintype "passive"))
      (node (ref "U1") (pin "12") (pinfunction "PJ0/SDIO0_12") (pintype "passive"))
    )
    (net (code "49") (name "/PJ1{slash}LRCK") (class "Default")
      (node (ref "C30") (pin "1") (pinfunction "1_1") (pintype "passive"))
      (node (ref "H2") (pin "19") (pinfunction "19_19") (pintype "passive"))
      (node (ref "R27") (pin "1") (pinfunction "1_1") (pintype "passive"))
      (node (ref "R27") (pin "2") (pinfunction "2_2") (pintype "passive"))
      (node (ref "U1") (pin "13") (pinfunction "PJ1/LRCK_13") (pintype "passive"))
    )
    (net (code "50") (name "/PJ2{slash}BCLK") (class "Default")
      (node (ref "C31") (pin "1") (pinfunction "1_1") (pintype "passive"))
      (node (ref "H2") (pin "17") (pinfunction "17_17") (pintype "passive"))
      (node (ref "R28") (pin "1") (pinfunction "1_1") (pintype "passive"))
      (node (ref "R28") (pin "2") (pinfunction "2_2") (pintype "passive"))
      (node (ref "U1") (pin "14") (pinfunction "PJ2/BCLK_14") (pintype "passive"))
    )
    (net (code "51") (name "/PJ3{slash}MCLK") (class "Default")
      (node (ref "C32") (pin "1") (pinfunction "1_1") (pintype "passive"))
      (node (ref "H2") (pin "15") (pinfunction "15_15") (pintype "passive"))
      (node (ref "R29") (pin "1") (pinfunction "1_1") (pintype "passive"))
      (node (ref "R29") (pin "2") (pinfunction "2_2") (pintype "passive"))
      (node (ref "U1") (pin "15") (pinfunction "PJ3/MCLK_15") (pintype "passive"))
    )
    (net (code "52") (name "/SYS_SWCLK") (class "Default")
      (node (ref "H5") (pin "2") (pinfunction "2_2") (pintype "passive"))
      (node (ref "U2") (pin "20") (pinfunction "PA14_20") (pintype "passive"))
    )
    (net (code "53") (name "/SYS_SWDIO") (class "Default")
      (node (ref "H5") (pin "1") (pinfunction "1_1") (pintype "passive"))
      (node (ref "U2") (pin "19") (pinfunction "PA13_19") (pintype "passive"))
    )
    (net (code "54") (name "/TMRB") (class "Default")
      (node (ref "H1") (pin "6") (pinfunction "6_6") (pintype "passive"))
      (node (ref "R23") (pin "2") (pinfunction "2_2") (pintype "passive"))
      (node (ref "U1") (pin "53") (pinfunction "TMRB_53") (pintype "passive"))
    )
    (net (code "55") (name "/USB_D+") (class "Default")
      (node (ref "D1") (pin "3") (pinfunction "3_3") (pintype "passive"))
      (node (ref "J1") (pin "A6") (pinfunction "Dp1_A6") (pintype "passive"))
      (node (ref "J1") (pin "B6") (pinfunction "Dp2_B6") (pintype "passive"))
      (node (ref "U2") (pin "17") (pinfunction "PA9/PA11_17") (pintype "passive"))
    )
    (net (code "56") (name "/USB_D-") (class "Default")
      (node (ref "D1") (pin "4") (pinfunction "4_4") (pintype "passive"))
      (node (ref "J1") (pin "A7") (pinfunction "Dn1_A7") (pintype "passive"))
      (node (ref "J1") (pin "B7") (pinfunction "Dn2_B7") (pintype "passive"))
      (node (ref "U2") (pin "18") (pinfunction "PA10/PA12_18") (pintype "passive"))
    )
    (net (code "57") (name "/XPD_CS_MEM") (class "Default")
      (node (ref "H3") (pin "3") (pinfunction "CS_MEM_3") (pintype "passive"))
      (node (ref "H6") (pin "3") (pinfunction "3_3") (pintype "passive"))
      (node (ref "R19") (pin "1") (pinfunction "1_1") (pintype "passive"))
      (node (ref "U1") (pin "37") (pinfunction "PB0_37") (pintype "passive"))
      (node (ref "U2") (pin "8") (pinfunction "PA2_8") (pintype "passive"))
      (node (ref "U3") (pin "1") (pinfunction "/CS_1") (pintype "passive"))
    )
    (net (code "58") (name "/XPD_CS_X2") (class "Default")
      (node (ref "H3") (pin "7") (pinfunction "CS_X2_7") (pintype "passive"))
      (node (ref "H6") (pin "7") (pinfunction "7_7") (pintype "passive"))
      (node (ref "R20") (pin "2") (pinfunction "2_2") (pintype "passive"))
      (node (ref "U1") (pin "38") (pinfunction "PB1_38") (pintype "passive"))
      (node (ref "U2") (pin "10") (pinfunction "PA4_10") (pintype "passive"))
    )
    (net (code "59") (name "/XPD_MISO") (class "Default")
      (node (ref "H3") (pin "4") (pinfunction "MISO_4") (pintype "passive"))
      (node (ref "H6") (pin "4") (pinfunction "4_4") (pintype "passive"))
      (node (ref "U1") (pin "30") (pinfunction "PG0/MISO0_30") (pintype "passive"))
      (node (ref "U2") (pin "12") (pinfunction "PA6_12") (pintype "passive"))
      (node (ref "U3") (pin "2") (pinfunction "SDO_2") (pintype "passive"))
    )
    (net (code "60") (name "/XPD_MOSI") (class "Default")
      (node (ref "H3") (pin "5") (pinfunction "MOSI_5") (pintype "passive"))
      (node (ref "H6") (pin "5") (pinfunction "5_5") (pintype "passive"))
      (node (ref "U1") (pin "31") (pinfunction "PG1/MOSI0_31") (pintype "passive"))
      (node (ref "U2") (pin "13") (pinfunction "PA7_13") (pintype "passive"))
      (node (ref "U3") (pin "5") (pinfunction "SDI_5") (pintype "passive"))
    )
    (net (code "61") (name "/XPD_RST") (class "Default")
      (node (ref "C19") (pin "1") (pinfunction "1_1") (pintype "passive"))
      (node (ref "D2") (pin "1") (pinfunction "1_1") (pintype "passive"))
      (node (ref "D3") (pin "1") (pinfunction "1_1") (pintype "passive"))
      (node (ref "D4") (pin "1") (pinfunction "1_1") (pintype "passive"))
      (node (ref "D5") (pin "1") (pinfunction "1_1") (pintype "passive"))
      (node (ref "D6") (pin "1") (pinfunction "1_1") (pintype "passive"))
      (node (ref "R1") (pin "1") (pinfunction "1_1") (pintype "passive"))
      (node (ref "U1") (pin "91") (pinfunction "/RESET_91") (pintype "passive"))
    )
    (net (code "62") (name "/XPD_SCK") (class "Default")
      (node (ref "H3") (pin "2") (pinfunction "SCK_2") (pintype "passive"))
      (node (ref "H6") (pin "2") (pinfunction "2_2") (pintype "passive"))
      (node (ref "U1") (pin "32") (pinfunction "PG2/SCK0_32") (pintype "passive"))
      (node (ref "U2") (pin "11") (pinfunction "PA5_11") (pintype "passive"))
      (node (ref "U3") (pin "6") (pinfunction "CLK_6") (pintype "passive"))
    )
    (net (code "63") (name "1V8") (class "Default")
      (node (ref "C16") (pin "1") (pinfunction "1_1") (pintype "passive"))
      (node (ref "C33") (pin "1") (pinfunction "1_1") (pintype "passive"))
      (node (ref "C34") (pin "1") (pinfunction "1_1") (pintype "passive"))
      (node (ref "C35") (pin "1") (pinfunction "1_1") (pintype "passive"))
      (node (ref "C36") (pin "1") (pinfunction "1_1") (pintype "passive"))
      (node (ref "C37") (pin "1") (pinfunction "1_1") (pintype "passive"))
      (node (ref "C5") (pin "1") (pinfunction "1_1") (pintype "passive"))
      (node (ref "C6") (pin "1") (pinfunction "1_1") (pintype "passive"))
      (node (ref "C7") (pin "1") (pinfunction "1_1") (pintype "passive"))
      (node (ref "C8") (pin "1") (pinfunction "1_1") (pintype "passive"))
      (node (ref "C9") (pin "1") (pinfunction "1_1") (pintype "passive"))
      (node (ref "R1") (pin "2") (pinfunction "2_2") (pintype "passive"))
      (node (ref "U1") (pin "1") (pinfunction "VADC_1") (pintype "passive"))
      (node (ref "U1") (pin "17") (pinfunction "VCCK_17") (pintype "input"))
      (node (ref "U1") (pin "35") (pinfunction "VCCK_35") (pintype "input"))
      (node (ref "U1") (pin "45") (pinfunction "VCC18XT_45") (pintype "input"))
      (node (ref "U1") (pin "50") (pinfunction "VPLL_50") (pintype "input"))
      (node (ref "U1") (pin "67") (pinfunction "VCCK_67") (pintype "input"))
      (node (ref "U1") (pin "7") (pinfunction "VREF_7") (pintype "passive"))
      (node (ref "U1") (pin "8") (pinfunction "VCC18ADC_8") (pintype "passive"))
      (node (ref "U1") (pin "95") (pinfunction "VLP_95") (pintype "input"))
      (node (ref "U1") (pin "98") (pinfunction "V18_98") (pintype "output"))
    )
    (net (code "64") (name "3V3") (class "Default")
      (node (ref "C10") (pin "1") (pinfunction "1_1") (pintype "passive"))
      (node (ref "C11") (pin "1") (pinfunction "1_1") (pintype "passive"))
      (node (ref "C12") (pin "1") (pinfunction "1_1") (pintype "passive"))
      (node (ref "C13") (pin "1") (pinfunction "1_1") (pintype "passive"))
      (node (ref "C15") (pin "1") (pinfunction "1_1") (pintype "passive"))
      (node (ref "C17") (pin "1") (pinfunction "1_1") (pintype "passive"))
      (node (ref "C20") (pin "1") (pinfunction "1_1") (pintype "passive"))
      (node (ref "C22") (pin "1") (pinfunction "1_1") (pintype "passive"))
      (node (ref "C23") (pin "1") (pinfunction "1_1") (pintype "passive"))
      (node (ref "H1") (pin "4") (pinfunction "4_4") (pintype "passive"))
      (node (ref "H3") (pin "1") (pinfunction "VCC_1") (pintype "passive"))
      (node (ref "H4") (pin "2") (pinfunction "2_2") (pintype "passive"))
      (node (ref "H6") (pin "1") (pinfunction "1_1") (pintype "passive"))
      (node (ref "LED1") (pin "4") (pinfunction "4_4") (pintype "passive"))
      (node (ref "R19") (pin "2") (pinfunction "2_2") (pintype "passive"))
      (node (ref "R2") (pin "2") (pinfunction "2_2") (pintype "passive"))
      (node (ref "U1") (pin "18") (pinfunction "VCC3IO_18") (pintype "input"))
      (node (ref "U1") (pin "34") (pinfunction "VCC3IO_34") (pintype "input"))
      (node (ref "U1") (pin "66") (pinfunction "VCC3IO_66") (pintype "input"))
      (node (ref "U1") (pin "79") (pinfunction "VCC3IO_79") (pintype "input"))
      (node (ref "U1") (pin "99") (pinfunction "VREG_99") (pintype "input"))
      (node (ref "U2") (pin "16") (pinfunction "VDD_16") (pintype "passive"))
      (node (ref "U2") (pin "5") (pinfunction "VDDA_5") (pintype "passive"))
      (node (ref "U2") (pin "7") (pinfunction "PA1_7") (pintype "passive"))
      (node (ref "U3") (pin "3") (pinfunction "/WP_3") (pintype "passive"))
      (node (ref "U3") (pin "7") (pinfunction "/HOLD_7") (pintype "passive"))
      (node (ref "U3") (pin "8") (pinfunction "VCC_8") (pintype "passive"))
      (node (ref "U4") (pin "3") (pinfunction "VOUT_3") (pintype "passive"))
    )
    (net (code "65") (name "5V") (class "Default")
      (node (ref "C14") (pin "1") (pinfunction "1_1") (pintype "passive"))
      (node (ref "H1") (pin "2") (pinfunction "2_2") (pintype "passive"))
      (node (ref "L1") (pin "2") (pinfunction "2_2") (pintype "passive"))
      (node (ref "U4") (pin "1") (pinfunction "VIN_1") (pintype "passive"))
    )
    (net (code "66") (name "GND") (class "Default")
      (node (ref "C1") (pin "2") (pinfunction "2_2") (pintype "passive"))
      (node (ref "C10") (pin "2") (pinfunction "2_2") (pintype "passive"))
      (node (ref "C11") (pin "2") (pinfunction "2_2") (pintype "passive"))
      (node (ref "C12") (pin "2") (pinfunction "2_2") (pintype "passive"))
      (node (ref "C13") (pin "2") (pinfunction "2_2") (pintype "passive"))
      (node (ref "C14") (pin "2") (pinfunction "2_2") (pintype "passive"))
      (node (ref "C15") (pin "2") (pinfunction "2_2") (pintype "passive"))
      (node (ref "C16") (pin "2") (pinfunction "2_2") (pintype "passive"))
      (node (ref "C17") (pin "2") (pinfunction "2_2") (pintype "passive"))
      (node (ref "C18") (pin "1") (pinfunction "1_1") (pintype "passive"))
      (node (ref "C19") (pin "2") (pinfunction "2_2") (pintype "passive"))
      (node (ref "C2") (pin "2") (pinfunction "2_2") (pintype "passive"))
      (node (ref "C20") (pin "2") (pinfunction "2_2") (pintype "passive"))
      (node (ref "C21") (pin "2") (pinfunction "2_2") (pintype "passive"))
      (node (ref "C22") (pin "2") (pinfunction "2_2") (pintype "passive"))
      (node (ref "C23") (pin "2") (pinfunction "2_2") (pintype "passive"))
      (node (ref "C25") (pin "2") (pinfunction "2_2") (pintype "passive"))
      (node (ref "C26") (pin "2") (pinfunction "2_2") (pintype "passive"))
      (node (ref "C27") (pin "2") (pinfunction "2_2") (pintype "passive"))
      (node (ref "C28") (pin "2") (pinfunction "2_2") (pintype "passive"))
      (node (ref "C29") (pin "2") (pinfunction "2_2") (pintype "passive"))
      (node (ref "C3") (pin "2") (pinfunction "2_2") (pintype "passive"))
      (node (ref "C30") (pin "2") (pinfunction "2_2") (pintype "passive"))
      (node (ref "C31") (pin "2") (pinfunction "2_2") (pintype "passive"))
      (node (ref "C32") (pin "2") (pinfunction "2_2") (pintype "passive"))
      (node (ref "C33") (pin "2") (pinfunction "2_2") (pintype "passive"))
      (node (ref "C34") (pin "2") (pinfunction "2_2") (pintype "passive"))
      (node (ref "C35") (pin "2") (pinfunction "2_2") (pintype "passive"))
      (node (ref "C36") (pin "2") (pinfunction "2_2") (pintype "passive"))
      (node (ref "C37") (pin "2") (pinfunction "2_2") (pintype "passive"))
      (node (ref "C4") (pin "2") (pinfunction "2_2") (pintype "passive"))
      (node (ref "C5") (pin "2") (pinfunction "2_2") (pintype "passive"))
      (node (ref "C6") (pin "2") (pinfunction "2_2") (pintype "passive"))
      (node (ref "C7") (pin "2") (pinfunction "2_2") (pintype "passive"))
      (node (ref "C8") (pin "2") (pinfunction "2_2") (pintype "passive"))
      (node (ref "C9") (pin "2") (pinfunction "2_2") (pintype "passive"))
      (node (ref "D1") (pin "1") (pinfunction "1_1") (pintype "passive"))
      (node (ref "D1") (pin "2") (pinfunction "2_2") (pintype "passive"))
      (node (ref "H1") (pin "1") (pinfunction "1_1") (pintype "passive"))
      (node (ref "H1") (pin "27") (pinfunction "27_27") (pintype "passive"))
      (node (ref "H1") (pin "28") (pinfunction "28_28") (pintype "passive"))
      (node (ref "H1") (pin "3") (pinfunction "3_3") (pintype "passive"))
      (node (ref "H1") (pin "7") (pinfunction "7_7") (pintype "passive"))
      (node (ref "H1") (pin "8") (pinfunction "8_8") (pintype "passive"))
      (node (ref "H2") (pin "16") (pinfunction "16_16") (pintype "passive"))
      (node (ref "H2") (pin "18") (pinfunction "18_18") (pintype "passive"))
      (node (ref "H2") (pin "2") (pinfunction "2_2") (pintype "passive"))
      (node (ref "H2") (pin "20") (pinfunction "20_20") (pintype "passive"))
      (node (ref "H2") (pin "22") (pinfunction "22_22") (pintype "passive"))
      (node (ref "H2") (pin "24") (pinfunction "24_24") (pintype "passive"))
      (node (ref "H2") (pin "26") (pinfunction "26_26") (pintype "passive"))
      (node (ref "H2") (pin "27") (pinfunction "27_27") (pintype "passive"))
      (node (ref "H2") (pin "28") (pinfunction "28_28") (pintype "passive"))
      (node (ref "H2") (pin "30") (pinfunction "30_30") (pintype "passive"))
      (node (ref "H2") (pin "32") (pinfunction "32_32") (pintype "passive"))
      (node (ref "H2") (pin "34") (pinfunction "34_34") (pintype "passive"))
      (node (ref "H2") (pin "36") (pinfunction "36_36") (pintype "passive"))
      (node (ref "H3") (pin "6") (pinfunction "GND_6") (pintype "passive"))
      (node (ref "H5") (pin "3") (pinfunction "3_3") (pintype "passive"))
      (node (ref "H6") (pin "6") (pinfunction "6_6") (pintype "passive"))
      (node (ref "J1") (pin "A1") (pinfunction "GND_A1") (pintype "passive"))
      (node (ref "J1") (pin "A12") (pinfunction "GND_A12") (pintype "passive"))
      (node (ref "J1") (pin "B1") (pinfunction "GND_B1") (pintype "passive"))
      (node (ref "J1") (pin "B12") (pinfunction "GND_B12") (pintype "passive"))
      (node (ref "LED2") (pin "2") (pinfunction "2_2") (pintype "passive"))
      (node (ref "LED3") (pin "2") (pinfunction "2_2") (pintype "passive"))
      (node (ref "LED4") (pin "2") (pinfunction "2_2") (pintype "passive"))
      (node (ref "M1") (pin "1") (pinfunction "1_1") (pintype "passive"))
      (node (ref "M2") (pin "1") (pinfunction "1_1") (pintype "passive"))
      (node (ref "M3") (pin "1") (pinfunction "1_1") (pintype "passive"))
      (node (ref "M4") (pin "1") (pinfunction "1_1") (pintype "passive"))
      (node (ref "Q1") (pin "E") (pinfunction "E_E") (pintype "passive"))
      (node (ref "Q2") (pin "E") (pinfunction "E_E") (pintype "passive"))
      (node (ref "Q3") (pin "E") (pinfunction "E_E") (pintype "passive"))
      (node (ref "R14") (pin "1") (pinfunction "1_1") (pintype "passive"))
      (node (ref "R18") (pin "1") (pinfunction "1_1") (pintype "passive"))
      (node (ref "R20") (pin "1") (pinfunction "1_1") (pintype "passive"))
      (node (ref "R4") (pin "1") (pinfunction "1_1") (pintype "passive"))
      (node (ref "R5") (pin "1") (pinfunction "1_1") (pintype "passive"))
      (node (ref "SW1") (pin "1") (pinfunction "1_1") (pintype "passive"))
      (node (ref "SW1") (pin "2") (pinfunction "2_2") (pintype "passive"))
      (node (ref "SW2") (pin "1") (pinfunction "1_1") (pintype "passive"))
      (node (ref "SW2") (pin "2") (pinfunction "2_2") (pintype "passive"))
      (node (ref "SW3") (pin "1") (pinfunction "1_1") (pintype "passive"))
      (node (ref "SW3") (pin "2") (pinfunction "2_2") (pintype "passive"))
      (node (ref "U1") (pin "0") (pinfunction "EPAD_0") (pintype "passive"))
      (node (ref "U1") (pin "100") (pinfunction "GNDREG_100") (pintype "passive"))
      (node (ref "U1") (pin "16") (pinfunction "GNDIOK_16") (pintype "passive"))
      (node (ref "U1") (pin "36") (pinfunction "GNDIOK_36") (pintype "passive"))
      (node (ref "U1") (pin "48") (pinfunction "GNDXT_48") (pintype "passive"))
      (node (ref "U1") (pin "51") (pinfunction "GNDPLL_51") (pintype "passive"))
      (node (ref "U1") (pin "6") (pinfunction "GNDADC_6") (pintype "passive"))
      (node (ref "U1") (pin "68") (pinfunction "GNDIOK_68") (pintype "passive"))
      (node (ref "U1") (pin "80") (pinfunction "GNDIO_80") (pintype "passive"))
      (node (ref "U1") (pin "9") (pinfunction "GND18ADC_9") (pintype "passive"))
      (node (ref "U1") (pin "94") (pinfunction "GNDLP_94") (pintype "passive"))
      (node (ref "U2") (pin "15") (pinfunction "VSS_15") (pintype "passive"))
      (node (ref "U3") (pin "4") (pinfunction "GND_4") (pintype "passive"))
      (node (ref "U4") (pin "2") (pinfunction "GND_2") (pintype "passive"))
    )
    (net (code "67") (name "Net-(C25-Pad1)") (class "Default")
      (node (ref "C25") (pin "1") (pinfunction "1_1") (pintype "passive"))
      (node (ref "R21") (pin "2") (pinfunction "2_2") (pintype "passive"))
      (node (ref "R22") (pin "1") (pinfunction "1_1") (pintype "passive"))
    )
    (net (code "68") (name "Net-(C26-Pad1)") (class "Default")
      (node (ref "C26") (pin "1") (pinfunction "1_1") (pintype "passive"))
      (node (ref "R22") (pin "2") (pinfunction "2_2") (pintype "passive"))
      (node (ref "R23") (pin "1") (pinfunction "1_1") (pintype "passive"))
    )
    (net (code "69") (name "Net-(D4-Pad2)") (class "Default")
      (node (ref "D4") (pin "2") (pinfunction "2_2") (pintype "passive"))
      (node (ref "H6") (pin "8") (pinfunction "8_8") (pintype "passive"))
    )
    (net (code "70") (name "Net-(D5-Pad2)") (class "Default")
      (node (ref "D5") (pin "2") (pinfunction "2_2") (pintype "passive"))
      (node (ref "SW3") (pin "3") (pinfunction "3_3") (pintype "passive"))
      (node (ref "SW3") (pin "4") (pinfunction "4_4") (pintype "passive"))
    )
    (net (code "71") (name "Net-(D6-Pad2)") (class "Default")
      (node (ref "D6") (pin "2") (pinfunction "2_2") (pintype "passive"))
      (node (ref "H2") (pin "1") (pinfunction "1_1") (pintype "passive"))
    )
    (net (code "72") (name "Net-(F1-Pad1)") (class "Default")
      (node (ref "F1") (pin "1") (pinfunction "1_1") (pintype "passive"))
      (node (ref "J1") (pin "A4") (pinfunction "VBUS_A4") (pintype "passive"))
      (node (ref "J1") (pin "A9") (pinfunction "VBUS_A9") (pintype "passive"))
      (node (ref "J1") (pin "B4") (pinfunction "VBUS_B4") (pintype "passive"))
      (node (ref "J1") (pin "B9") (pinfunction "VBUS_B9") (pintype "passive"))
    )
    (net (code "73") (name "Net-(H3-RST)") (class "Default")
      (node (ref "D2") (pin "2") (pinfunction "2_2") (pintype "passive"))
      (node (ref "H3") (pin "8") (pinfunction "RST_8") (pintype "passive"))
    )
    (net (code "74") (name "Net-(J1-CC1)") (class "Default")
      (node (ref "J1") (pin "A5") (pinfunction "CC1_A5") (pintype "passive"))
      (node (ref "R5") (pin "2") (pinfunction "2_2") (pintype "passive"))
    )
    (net (code "75") (name "Net-(J1-CC2)") (class "Default")
      (node (ref "J1") (pin "B5") (pinfunction "CC2_B5") (pintype "passive"))
      (node (ref "R4") (pin "2") (pinfunction "2_2") (pintype "passive"))
    )
    (net (code "76") (name "Net-(J1-Shell)") (class "Default")
      (node (ref "J1") (pin "0") (pinfunction "Shell_0") (pintype "passive"))
      (node (ref "R18") (pin "2") (pinfunction "2_2") (pintype "passive"))
    )
    (net (code "77") (name "Net-(LED1-Pad1)") (class "Default")
      (node (ref "LED1") (pin "1") (pinfunction "1_1") (pintype "passive"))
      (node (ref "R6") (pin "1") (pinfunction "1_1") (pintype "passive"))
    )
    (net (code "78") (name "Net-(LED1-Pad2)") (class "Default")
      (node (ref "LED1") (pin "2") (pinfunction "2_2") (pintype "passive"))
      (node (ref "R7") (pin "1") (pinfunction "1_1") (pintype "passive"))
    )
    (net (code "79") (name "Net-(LED1-Pad3)") (class "Default")
      (node (ref "LED1") (pin "3") (pinfunction "3_3") (pintype "passive"))
      (node (ref "R8") (pin "2") (pinfunction "2_2") (pintype "passive"))
    )
    (net (code "80") (name "Net-(LED2-Pad1)") (class "Default")
      (node (ref "LED2") (pin "1") (pinfunction "1_1") (pintype "passive"))
      (node (ref "R15") (pin "2") (pinfunction "2_2") (pintype "passive"))
    )
    (net (code "81") (name "Net-(LED3-Pad1)") (class "Default")
      (node (ref "LED3") (pin "1") (pinfunction "1_1") (pintype "passive"))
      (node (ref "R16") (pin "2") (pinfunction "2_2") (pintype "passive"))
    )
    (net (code "82") (name "Net-(LED4-Pad1)") (class "Default")
      (node (ref "LED4") (pin "1") (pinfunction "1_1") (pintype "passive"))
      (node (ref "R17") (pin "1") (pinfunction "1_1") (pintype "passive"))
    )
    (net (code "83") (name "Net-(Q1-PadB)") (class "Default")
      (node (ref "Q1") (pin "B") (pinfunction "B_B") (pintype "passive"))
      (node (ref "R9") (pin "2") (pinfunction "2_2") (pintype "passive"))
    )
    (net (code "84") (name "Net-(Q1-PadC)") (class "Default")
      (node (ref "Q1") (pin "C") (pinfunction "C_C") (pintype "passive"))
      (node (ref "R6") (pin "2") (pinfunction "2_2") (pintype "passive"))
    )
    (net (code "85") (name "Net-(Q2-PadB)") (class "Default")
      (node (ref "Q2") (pin "B") (pinfunction "B_B") (pintype "passive"))
      (node (ref "R11") (pin "2") (pinfunction "2_2") (pintype "passive"))
    )
    (net (code "86") (name "Net-(Q2-PadC)") (class "Default")
      (node (ref "Q2") (pin "C") (pinfunction "C_C") (pintype "passive"))
      (node (ref "R7") (pin "2") (pinfunction "2_2") (pintype "passive"))
    )
    (net (code "87") (name "Net-(Q3-PadB)") (class "Default")
      (node (ref "Q3") (pin "B") (pinfunction "B_B") (pintype "passive"))
      (node (ref "R12") (pin "2") (pinfunction "2_2") (pintype "passive"))
    )
    (net (code "88") (name "Net-(Q3-PadC)") (class "Default")
      (node (ref "Q3") (pin "C") (pinfunction "C_C") (pintype "passive"))
      (node (ref "R8") (pin "1") (pinfunction "1_1") (pintype "passive"))
    )
    (net (code "89") (name "Net-(R10-Pad2)") (class "Default")
      (node (ref "R10") (pin "2") (pinfunction "2_2") (pintype "passive"))
      (node (ref "SW1") (pin "3") (pinfunction "3_3") (pintype "passive"))
      (node (ref "SW1") (pin "4") (pinfunction "4_4") (pintype "passive"))
    )
    (net (code "90") (name "Net-(R13-Pad2)") (class "Default")
      (node (ref "R13") (pin "2") (pinfunction "2_2") (pintype "passive"))
      (node (ref "SW2") (pin "3") (pinfunction "3_3") (pintype "passive"))
      (node (ref "SW2") (pin "4") (pinfunction "4_4") (pintype "passive"))
    )
    (net (code "91") (name "Net-(U1-RCI)") (class "Default")
      (node (ref "C18") (pin "2") (pinfunction "2_2") (pintype "passive"))
      (node (ref "R3") (pin "2") (pinfunction "2_2") (pintype "passive"))
      (node (ref "U1") (pin "93") (pinfunction "RCI_93") (pintype "passive"))
    )
    (net (code "92") (name "Net-(U1-RCO)") (class "Default")
      (node (ref "R3") (pin "1") (pinfunction "1_1") (pintype "passive"))
      (node (ref "U1") (pin "92") (pinfunction "RCO_92") (pintype "passive"))
    )
    (net (code "93") (name "Net-(U1-REGEN)") (class "Default")
      (node (ref "R2") (pin "1") (pinfunction "1_1") (pintype "passive"))
      (node (ref "U1") (pin "97") (pinfunction "REGEN_97") (pintype "passive"))
    )
    (net (code "94") (name "Net-(U1-VDC)") (class "Default")
      (node (ref "C24") (pin "2") (pinfunction "2_2") (pintype "passive"))
      (node (ref "R21") (pin "1") (pinfunction "1_1") (pintype "passive"))
      (node (ref "U1") (pin "49") (pinfunction "VDC_49") (pintype "passive"))
    )
    (net (code "95") (name "Net-(U1-XTI)") (class "Default")
      (node (ref "C1") (pin "1") (pinfunction "1_1") (pintype "passive"))
      (node (ref "U1") (pin "46") (pinfunction "XTI_46") (pintype "passive"))
      (node (ref "X1") (pin "1") (pinfunction "1_1") (pintype "passive"))
    )
    (net (code "96") (name "Net-(U1-XTO)") (class "Default")
      (node (ref "C2") (pin "1") (pinfunction "1_1") (pintype "passive"))
      (node (ref "C24") (pin "1") (pinfunction "1_1") (pintype "passive"))
      (node (ref "U1") (pin "47") (pinfunction "XTO_47") (pintype "passive"))
      (node (ref "X1") (pin "2") (pinfunction "2_2") (pintype "passive"))
    )
    (net (code "97") (name "Net-(U2-NRST)") (class "Default")
      (node (ref "C21") (pin "1") (pinfunction "1_1") (pintype "passive"))
      (node (ref "U2") (pin "4") (pinfunction "NRST_4") (pintype "passive"))
    )
    (net (code "98") (name "Net-(U2-PA0)") (class "Default")
      (node (ref "D3") (pin "2") (pinfunction "2_2") (pintype "passive"))
      (node (ref "U2") (pin "6") (pinfunction "PA0_6") (pintype "passive"))
    )
    (net (code "99") (name "Net-(U2-PB1)") (class "Default")
      (node (ref "R15") (pin "1") (pinfunction "1_1") (pintype "passive"))
      (node (ref "U2") (pin "14") (pinfunction "PB1_14") (pintype "passive"))
    )
    (net (code "100") (name "Net-(U2-PB8-BOOT0)") (class "Default")
      (node (ref "H4") (pin "1") (pinfunction "1_1") (pintype "passive"))
      (node (ref "R14") (pin "2") (pinfunction "2_2") (pintype "passive"))
      (node (ref "U2") (pin "1") (pinfunction "PB8-BOOT0_1") (pintype "passive"))
    )
    (net (code "101") (name "Net-(U2-PF0)") (class "Default")
      (node (ref "R16") (pin "1") (pinfunction "1_1") (pintype "passive"))
      (node (ref "U2") (pin "2") (pinfunction "PF0_2") (pintype "passive"))
    )
    (net (code "102") (name "Net-(U2-PF1)") (class "Default")
      (node (ref "R17") (pin "2") (pinfunction "2_2") (pintype "passive"))
      (node (ref "U2") (pin "3") (pinfunction "PF1_3") (pintype "passive"))
    )
    (net (code "103") (name "VBUS") (class "Default")
      (node (ref "C3") (pin "1") (pinfunction "1_1") (pintype "passive"))
      (node (ref "C4") (pin "1") (pinfunction "1_1") (pintype "passive"))
      (node (ref "D1") (pin "5") (pinfunction "5_5") (pintype "passive"))
      (node (ref "F1") (pin "2") (pinfunction "2_2") (pintype "passive"))
      (node (ref "L1") (pin "1") (pinfunction "1_1") (pintype "passive"))
    )
    (net (code "104") (name "unconnected-(J1-SBU1-PadA8)") (class "Default")
      (node (ref "J1") (pin "A8") (pinfunction "SBU1_A8") (pintype "passive+no_connect"))
    )
    (net (code "105") (name "unconnected-(J1-SBU2-PadB8)") (class "Default")
      (node (ref "J1") (pin "B8") (pinfunction "SBU2_B8") (pintype "passive+no_connect"))
    )
    (net (code "106") (name "unconnected-(U1-LPPD-Pad96)") (class "Default")
      (node (ref "U1") (pin "96") (pinfunction "LPPD_96") (pintype "output+no_connect"))
    )
    (net (code "107") (name "unconnected-(U1-PB2-Pad39)") (class "Default")
      (node (ref "U1") (pin "39") (pinfunction "PB2_39") (pintype "passive+no_connect"))
    )
    (net (code "108") (name "unconnected-(U1-PG3{slash}SEN0-Pad33)") (class "Default")
      (node (ref "U1") (pin "33") (pinfunction "PG3/SEN0_33") (pintype "passive+no_connect"))
    )
    (net (code "109") (name "unconnected-(U1-PORDIS-Pad89)") (class "Default")
      (node (ref "U1") (pin "89") (pinfunction "PORDIS_89") (pintype "passive+no_connect"))
    )
    (net (code "110") (name "unconnected-(U1-PORRES-Pad90)") (class "Default")
      (node (ref "U1") (pin "90") (pinfunction "PORRES_90") (pintype "passive+no_connect"))
    )
    (net (code "111") (name "unconnected-(U1-TESTP_IP-Pad77)") (class "Default")
      (node (ref "U1") (pin "77") (pinfunction "TESTP_IP_77") (pintype "passive+no_connect"))
    )
    (net (code "112") (name "unconnected-(U1-TEST_M-Pad78)") (class "Default")
      (node (ref "U1") (pin "78") (pinfunction "TEST_M_78") (pintype "passive+no_connect"))
    )
    (net (code "113") (name "unconnected-(U1-mbist_PS_sel-Pad27)") (class "Default")
      (node (ref "U1") (pin "27") (pinfunction "mbist_PS_sel_27") (pintype "passive+no_connect"))
    )
    (net (code "114") (name "unconnected-(U1-mbist_hold_1-Pad28)") (class "Default")
      (node (ref "U1") (pin "28") (pinfunction "mbist_hold_1_28") (pintype "passive+no_connect"))
    )
    (net (code "115") (name "unconnected-(U1-scan_en-Pad75)") (class "Default")
      (node (ref "U1") (pin "75") (pinfunction "scan_en_75") (pintype "passive+no_connect"))
    )
    (net (code "116") (name "unconnected-(U1-scan_test-Pad76)") (class "Default")
      (node (ref "U1") (pin "76") (pinfunction "scan_test_76") (pintype "passive+no_connect"))
    )
    (net (code "117") (name "unconnected-(U2-PA3-Pad9)") (class "Default")
      (node (ref "U2") (pin "9") (pinfunction "PA3_9") (pintype "passive+no_connect"))
    )
  )
)
